# LEDS_BOARD.net
KiCad netlist of a schematic drawn in Altium Designer
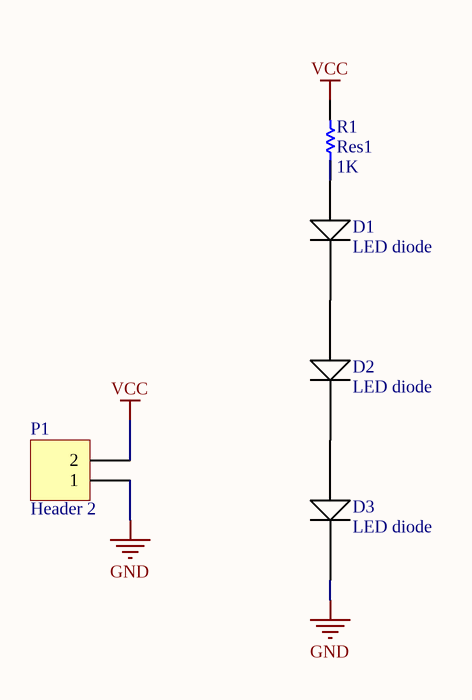
[diagram p0: LEDS_BOARD.SchDoc]

(export (version "E")
  (design (tool "Eeschema 10.0.6"))
  (components
    (comp (ref "D1")
      (value "LED diode")
      (footprint "led_UV")
      (description "standar through hole led diode")
      (libsource (lib "INSOLTOR_LIB") (part "LED_UV"))
    )
    (comp (ref "D2")
      (value "LED diode")
      (footprint "led_UV")
      (description "standar through hole led diode")
      (libsource (lib "INSOLTOR_LIB") (part "LED_UV"))
    )
    (comp (ref "D3")
      (value "LED diode")
      (footprint "led_UV")
      (description "standar through hole led diode")
      (libsource (lib "INSOLTOR_LIB") (part "LED_UV"))
    )
    (comp (ref "P1")
      (value "Header 2")
      (footprint "HDR1X2")
      (description "Header, 2-Pin")
      (fields (field (name "PUBLISHER") "Altium Limited"))
      (libsource (lib "Miscellaneous Connectors") (part "Header 2"))
    )
    (comp (ref "R1")
      (value "Res1")
      (footprint "AXIAL-0.3")
      (description "Resistor")
      (fields (field (name "ALTIUM_VALUE") "1K") (field (name "PUBLISHER") "Altium Limited"))
      (libsource (lib "Miscellaneous Devices") (part "Res1"))
    )
  )
  (nets
    (net (code "1") (name "GND") (class "Default")
      (node (ref "D3") (pin "0") (pinfunction "0_0") (pintype "passive"))
      (node (ref "P1") (pin "1") (pinfunction "1_1") (pintype "passive"))
    )
    (net (code "2") (name "Net-(D1-Pad0)") (class "Default")
      (node (ref "D1") (pin "0") (pinfunction "0_0") (pintype "passive"))
      (node (ref "D2") (pin "1") (pinfunction "1_1") (pintype "passive"))
    )
    (net (code "3") (name "Net-(D1-Pad1)") (class "Default")
      (node (ref "D1") (pin "1") (pinfunction "1_1") (pintype "passive"))
      (node (ref "R1") (pin "1") (pinfunction "1_1") (pintype "passive"))
    )
    (net (code "4") (name "Net-(D2-Pad0)") (class "Default")
      (node (ref "D2") (pin "0") (pinfunction "0_0") (pintype "passive"))
      (node (ref "D3") (pin "1") (pinfunction "1_1") (pintype "passive"))
    )
    (net (code "5") (name "VCC") (class "Default")
      (node (ref "P1") (pin "2") (pinfunction "2_2") (pintype "passive"))
      (node (ref "R1") (pin "2") (pinfunction "2_2") (pintype "passive"))
    )
  )
)
